# a101-fader.net
KiCad netlist of a schematic drawn in EAGLE
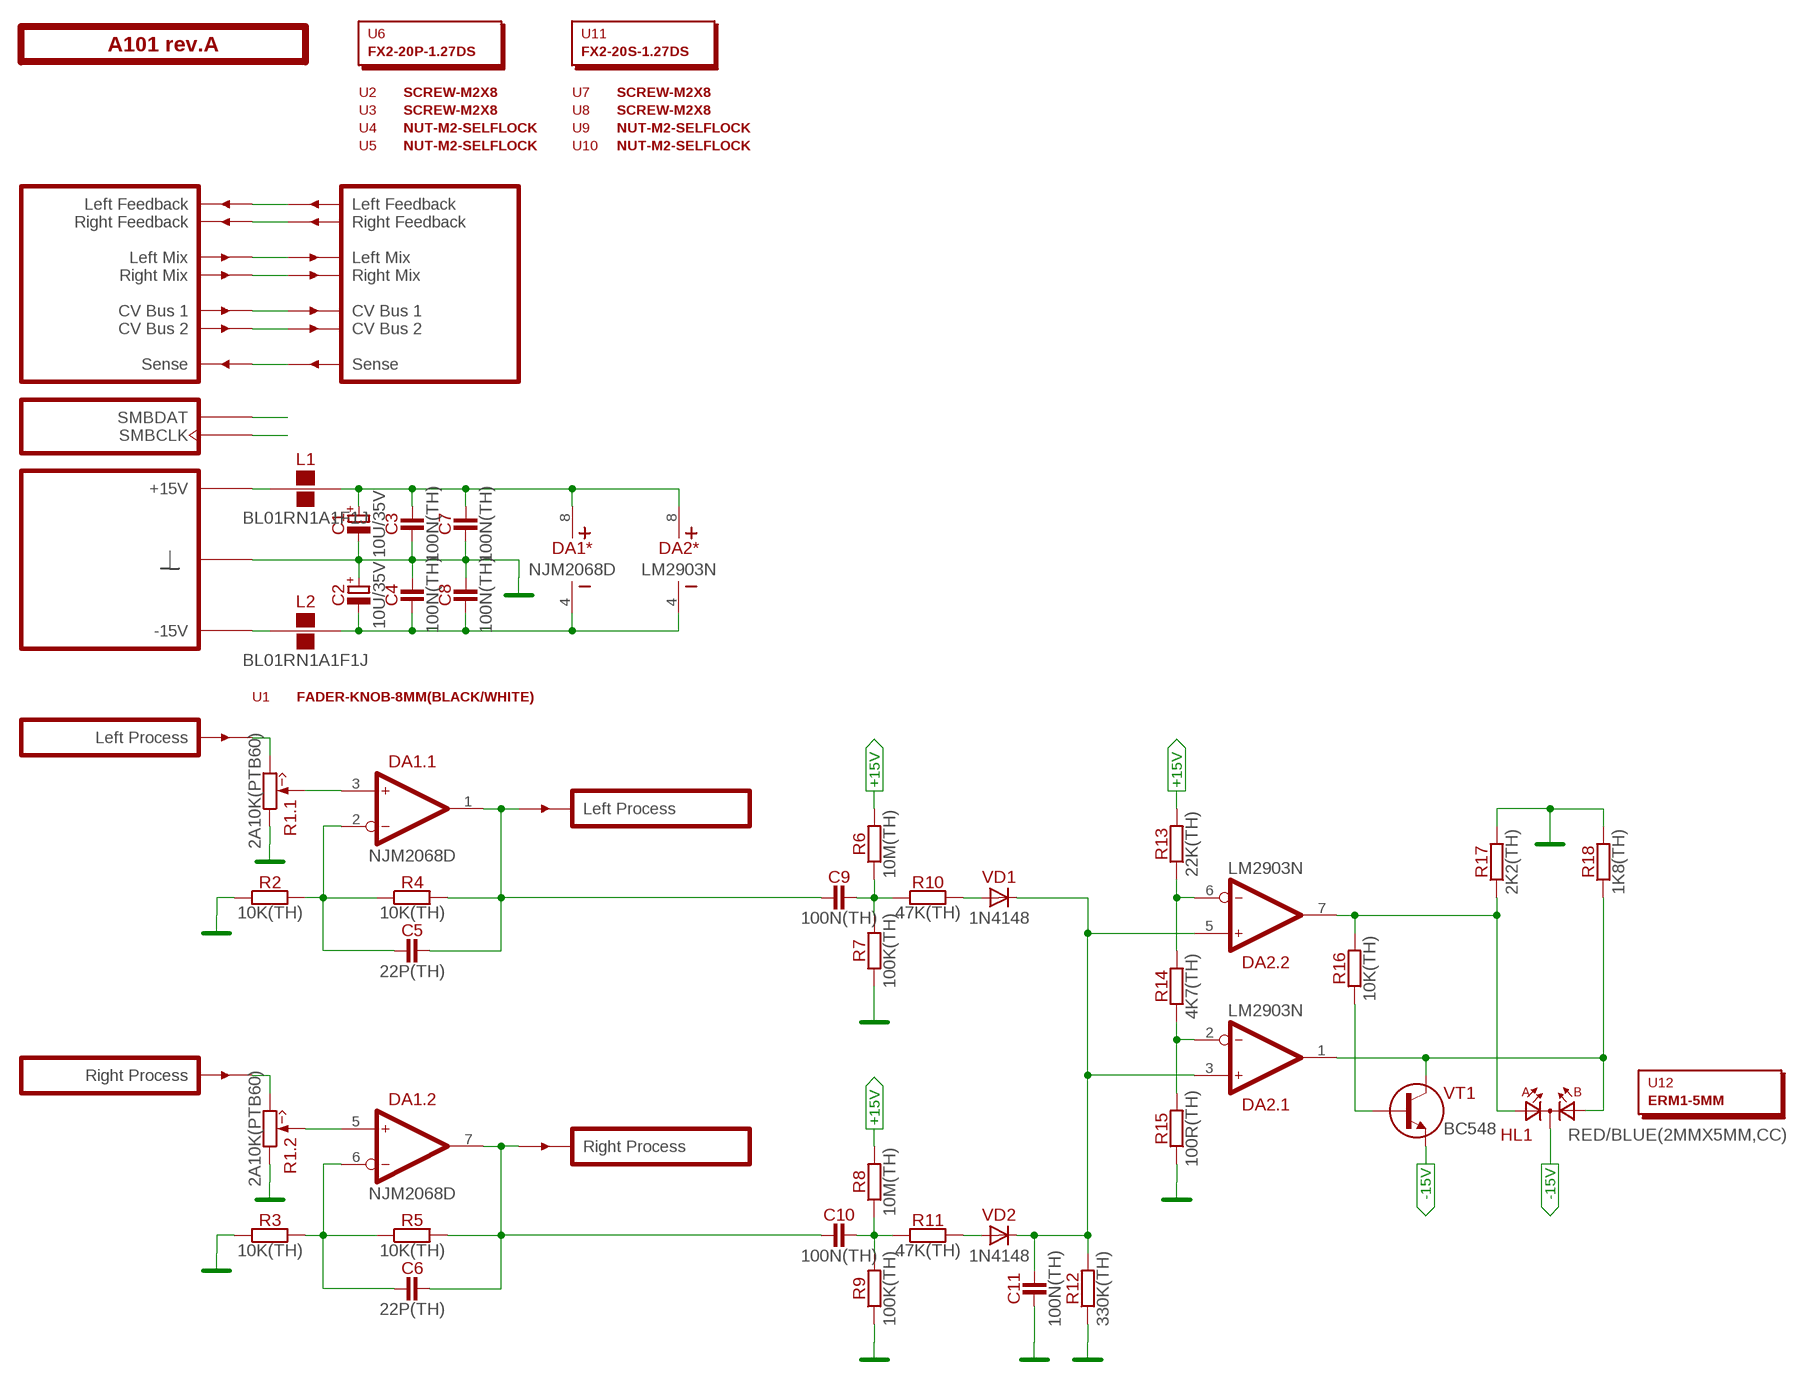
[diagram p0: schematic, sheet 1]

(export (version "E")
  (design (tool "Eeschema 10.0.6"))
  (components
    (comp (ref "C1")
      (value "10U/35V")
      (footprint "eagle-import:E2-5")
      (libsource (lib "eagle-import") (part "?10U/35V"))
    )
    (comp (ref "C2")
      (value "10U/35V")
      (footprint "eagle-import:E2-5")
      (libsource (lib "eagle-import") (part "?10U/35V"))
    )
    (comp (ref "C3")
      (value "100N(TH)")
      (footprint "eagle-import:C050-024X044")
      (libsource (lib "eagle-import") (part "?100N(TH)"))
    )
    (comp (ref "C4")
      (value "100N(TH)")
      (footprint "eagle-import:C050-024X044")
      (libsource (lib "eagle-import") (part "?100N(TH)"))
    )
    (comp (ref "C5")
      (value "22P(TH)")
      (footprint "eagle-import:C050-024X044")
      (libsource (lib "eagle-import") (part "?22P(TH)"))
    )
    (comp (ref "C6")
      (value "22P(TH)")
      (footprint "eagle-import:C050-024X044")
      (libsource (lib "eagle-import") (part "?22P(TH)"))
    )
    (comp (ref "C7")
      (value "100N(TH)")
      (footprint "eagle-import:C050-024X044")
      (libsource (lib "eagle-import") (part "?100N(TH)"))
    )
    (comp (ref "C8")
      (value "100N(TH)")
      (footprint "eagle-import:C050-024X044")
      (libsource (lib "eagle-import") (part "?100N(TH)"))
    )
    (comp (ref "C9")
      (value "100N(TH)")
      (footprint "eagle-import:C050-024X044")
      (libsource (lib "eagle-import") (part "?100N(TH)"))
    )
    (comp (ref "C10")
      (value "100N(TH)")
      (footprint "eagle-import:C050-024X044")
      (libsource (lib "eagle-import") (part "?100N(TH)"))
    )
    (comp (ref "C11")
      (value "100N(TH)")
      (footprint "eagle-import:C050-024X044")
      (libsource (lib "eagle-import") (part "?100N(TH)"))
    )
    (comp (ref "DA1")
      (value "NJM2068D")
      (footprint "eagle-import:DIP-8")
      (libsource (lib "eagle-import") (part "NJM2068D"))
    )
    (comp (ref "DA2")
      (value "LM2903N")
      (footprint "eagle-import:DIP-8")
      (libsource (lib "eagle-import") (part "LM2903N"))
    )
    (comp (ref "HL1")
      (value "RED/BLUE(2MMX5MM,CC)")
      (footprint "eagle-import:LED2X5-3PIN")
      (libsource (lib "eagle-import") (part "?(2MMX5MM,CC)RED/BLUE"))
    )
    (comp (ref "L1")
      (value "BL01RN1A1F1J")
      (footprint "eagle-import:BL01RN1A")
      (libsource (lib "eagle-import") (part "BL01RN1A?1F1J"))
    )
    (comp (ref "L2")
      (value "BL01RN1A1F1J")
      (footprint "eagle-import:BL01RN1A")
      (libsource (lib "eagle-import") (part "BL01RN1A?1F1J"))
    )
    (comp (ref "PCB1")
      (value "A101 rev.A")
      (footprint "eagle-import:ST2-BOARD-50")
      (libsource (lib "eagle-import") (part "ST2-BOARD-?50"))
    )
    (comp (ref "R1")
      (value "2A10K(PTB60)")
      (footprint "eagle-import:PTB6044")
      (libsource (lib "eagle-import") (part "2?(PTB60)A10K"))
    )
    (comp (ref "R2")
      (value "10K(TH)")
      (footprint "eagle-import:R-0207_10")
      (libsource (lib "eagle-import") (part "?10K(TH)"))
    )
    (comp (ref "R3")
      (value "10K(TH)")
      (footprint "eagle-import:R-0207_10")
      (libsource (lib "eagle-import") (part "?10K(TH)"))
    )
    (comp (ref "R4")
      (value "10K(TH)")
      (footprint "eagle-import:R-0207_10")
      (libsource (lib "eagle-import") (part "?10K(TH)"))
    )
    (comp (ref "R5")
      (value "10K(TH)")
      (footprint "eagle-import:R-0207_10")
      (libsource (lib "eagle-import") (part "?10K(TH)"))
    )
    (comp (ref "R6")
      (value "10M(TH)")
      (footprint "eagle-import:R-0207_10")
      (libsource (lib "eagle-import") (part "?10M(TH)"))
    )
    (comp (ref "R7")
      (value "100K(TH)")
      (footprint "eagle-import:R-0207_10")
      (libsource (lib "eagle-import") (part "?100K(TH)"))
    )
    (comp (ref "R8")
      (value "10M(TH)")
      (footprint "eagle-import:R-0207_10")
      (libsource (lib "eagle-import") (part "?10M(TH)"))
    )
    (comp (ref "R9")
      (value "100K(TH)")
      (footprint "eagle-import:R-0207_10")
      (libsource (lib "eagle-import") (part "?100K(TH)"))
    )
    (comp (ref "R10")
      (value "47K(TH)")
      (footprint "eagle-import:R-0207_10")
      (libsource (lib "eagle-import") (part "?47K(TH)"))
    )
    (comp (ref "R11")
      (value "47K(TH)")
      (footprint "eagle-import:R-0207_10")
      (libsource (lib "eagle-import") (part "?47K(TH)"))
    )
    (comp (ref "R12")
      (value "330K(TH)")
      (footprint "eagle-import:R-0207_10")
      (libsource (lib "eagle-import") (part "?330K(TH)"))
    )
    (comp (ref "R13")
      (value "22K(TH)")
      (footprint "eagle-import:R-0207_10")
      (libsource (lib "eagle-import") (part "?22K(TH)"))
    )
    (comp (ref "R14")
      (value "4K7(TH)")
      (footprint "eagle-import:R-0207_10")
      (libsource (lib "eagle-import") (part "?4K7(TH)"))
    )
    (comp (ref "R15")
      (value "100R(TH)")
      (footprint "eagle-import:R-0207_10")
      (libsource (lib "eagle-import") (part "?100R(TH)"))
    )
    (comp (ref "R16")
      (value "10K(TH)")
      (footprint "eagle-import:R-0207_10")
      (libsource (lib "eagle-import") (part "?10K(TH)"))
    )
    (comp (ref "R17")
      (value "2K2(TH)")
      (footprint "eagle-import:R-0207_10")
      (libsource (lib "eagle-import") (part "?2K2(TH)"))
    )
    (comp (ref "R18")
      (value "1K8(TH)")
      (footprint "eagle-import:R-0207_10")
      (libsource (lib "eagle-import") (part "?1K8(TH)"))
    )
    (comp (ref "U1")
      (value "FADER-KNOB-8MM(BLACK/WHITE)")
      (footprint "eagle-import:EMPTY")
      (libsource (lib "eagle-import") (part "?FADER-KNOB-8MM(BLACK/WHITE)"))
    )
    (comp (ref "U2")
      (value "SCREW-M2X8")
      (footprint "eagle-import:EMPTY")
      (libsource (lib "eagle-import") (part "?SCREW-M2X8"))
    )
    (comp (ref "U3")
      (value "SCREW-M2X8")
      (footprint "eagle-import:EMPTY")
      (libsource (lib "eagle-import") (part "?SCREW-M2X8"))
    )
    (comp (ref "U4")
      (value "NUT-M2-SELFLOCK")
      (footprint "eagle-import:EMPTY")
      (libsource (lib "eagle-import") (part "?NUT-M2-SELFLOCK"))
    )
    (comp (ref "U5")
      (value "NUT-M2-SELFLOCK")
      (footprint "eagle-import:EMPTY")
      (libsource (lib "eagle-import") (part "?NUT-M2-SELFLOCK"))
    )
    (comp (ref "U6")
      (value "FX2-20P-1.27DS")
      (footprint "eagle-import:EMPTY")
      (libsource (lib "eagle-import") (part "?FX2-20P-1.27DS"))
    )
    (comp (ref "U7")
      (value "SCREW-M2X8")
      (footprint "eagle-import:EMPTY")
      (libsource (lib "eagle-import") (part "?SCREW-M2X8"))
    )
    (comp (ref "U8")
      (value "SCREW-M2X8")
      (footprint "eagle-import:EMPTY")
      (libsource (lib "eagle-import") (part "?SCREW-M2X8"))
    )
    (comp (ref "U9")
      (value "NUT-M2-SELFLOCK")
      (footprint "eagle-import:EMPTY")
      (libsource (lib "eagle-import") (part "?NUT-M2-SELFLOCK"))
    )
    (comp (ref "U10")
      (value "NUT-M2-SELFLOCK")
      (footprint "eagle-import:EMPTY")
      (libsource (lib "eagle-import") (part "?NUT-M2-SELFLOCK"))
    )
    (comp (ref "U11")
      (value "FX2-20S-1.27DS")
      (footprint "eagle-import:EMPTY")
      (libsource (lib "eagle-import") (part "?FX2-20S-1.27DS"))
    )
    (comp (ref "U12")
      (value "ERM1-5MM")
      (footprint "eagle-import:EMPTY")
      (libsource (lib "eagle-import") (part "?ERM1-5MM"))
    )
    (comp (ref "VD1")
      (value "1N4148")
      (footprint "eagle-import:DO35-7")
      (libsource (lib "eagle-import") (part "?1N4148"))
    )
    (comp (ref "VD2")
      (value "1N4148")
      (footprint "eagle-import:DO35-7")
      (libsource (lib "eagle-import") (part "?1N4148"))
    )
    (comp (ref "VT1")
      (value "BC548")
      (footprint "eagle-import:TO92")
      (libsource (lib "eagle-import") (part "?BC548"))
    )
  )
  (nets
    (net (code "1") (name "+15V") (class "Default")
      (node (ref "R13") (pin "2") (pinfunction "2_2") (pintype "passive"))
      (node (ref "R6") (pin "2") (pinfunction "2_2") (pintype "passive"))
      (node (ref "R8") (pin "2") (pinfunction "2_2") (pintype "passive"))
    )
    (net (code "2") (name "-15V") (class "Default")
      (node (ref "HL1") (pin "K") (pinfunction "K_K") (pintype "passive"))
      (node (ref "VT1") (pin "3") (pinfunction "E_3") (pintype "passive"))
    )
    (net (code "3") (name "GND") (class "Default")
      (node (ref "C1") (pin "-") (pinfunction "-_-") (pintype "passive"))
      (node (ref "C11") (pin "1") (pinfunction "1_1") (pintype "passive"))
      (node (ref "C2") (pin "+") (pinfunction "+_+") (pintype "passive"))
      (node (ref "C3") (pin "1") (pinfunction "1_1") (pintype "passive"))
      (node (ref "C4") (pin "2") (pinfunction "2_2") (pintype "passive"))
      (node (ref "C7") (pin "1") (pinfunction "1_1") (pintype "passive"))
      (node (ref "C8") (pin "2") (pinfunction "2_2") (pintype "passive"))
      (node (ref "PCB1") (pin "B4") (pinfunction "GND_B4") (pintype "bidirectional"))
      (node (ref "PCB1") (pin "B4'") (pinfunction "GND_B4'") (pintype "bidirectional"))
      (node (ref "PCB1") (pin "B5") (pinfunction "GND_B5") (pintype "bidirectional"))
      (node (ref "PCB1") (pin "B5'") (pinfunction "GND_B5'") (pintype "bidirectional"))
      (node (ref "PCB1") (pin "B6") (pinfunction "GND_B6") (pintype "bidirectional"))
      (node (ref "PCB1") (pin "B6'") (pinfunction "GND_B6'") (pintype "bidirectional"))
      (node (ref "PCB1") (pin "B7") (pinfunction "GND_B7") (pintype "bidirectional"))
      (node (ref "PCB1") (pin "B7'") (pinfunction "GND_B7'") (pintype "bidirectional"))
      (node (ref "PCB1") (pin "B8") (pinfunction "GND_B8") (pintype "bidirectional"))
      (node (ref "PCB1") (pin "B8'") (pinfunction "GND_B8'") (pintype "bidirectional"))
      (node (ref "R1") (pin "A1") (pinfunction "CCW_A1") (pintype "passive"))
      (node (ref "R1") (pin "B1") (pinfunction "CCW_B1") (pintype "passive"))
      (node (ref "R12") (pin "1") (pinfunction "1_1") (pintype "passive"))
      (node (ref "R15") (pin "1") (pinfunction "1_1") (pintype "passive"))
      (node (ref "R17") (pin "2") (pinfunction "2_2") (pintype "passive"))
      (node (ref "R18") (pin "2") (pinfunction "2_2") (pintype "passive"))
      (node (ref "R2") (pin "1") (pinfunction "1_1") (pintype "passive"))
      (node (ref "R3") (pin "1") (pinfunction "1_1") (pintype "passive"))
      (node (ref "R7") (pin "1") (pinfunction "1_1") (pintype "passive"))
      (node (ref "R9") (pin "1") (pinfunction "1_1") (pintype "passive"))
    )
    (net (code "4") (name "Net-(C9-Pad2)") (class "Default")
      (node (ref "C9") (pin "2") (pinfunction "2_2") (pintype "passive"))
      (node (ref "R10") (pin "1") (pinfunction "1_1") (pintype "passive"))
      (node (ref "R6") (pin "1") (pinfunction "1_1") (pintype "passive"))
      (node (ref "R7") (pin "2") (pinfunction "2_2") (pintype "passive"))
    )
    (net (code "5") (name "Net-(C10-Pad2)") (class "Default")
      (node (ref "C10") (pin "2") (pinfunction "2_2") (pintype "passive"))
      (node (ref "R11") (pin "1") (pinfunction "1_1") (pintype "passive"))
      (node (ref "R8") (pin "1") (pinfunction "1_1") (pintype "passive"))
      (node (ref "R9") (pin "2") (pinfunction "2_2") (pintype "passive"))
    )
    (net (code "6") (name "Net-(DA1A-V+)") (class "Default")
      (node (ref "C1") (pin "+") (pinfunction "+_+") (pintype "passive"))
      (node (ref "C3") (pin "2") (pinfunction "2_2") (pintype "passive"))
      (node (ref "C7") (pin "2") (pinfunction "2_2") (pintype "passive"))
      (node (ref "DA1") (pin "8") (pinfunction "V+_8") (pintype "power_in"))
      (node (ref "DA2") (pin "8") (pinfunction "V+_8") (pintype "power_in"))
      (node (ref "L1") (pin "2") (pinfunction "2_2") (pintype "passive"))
    )
    (net (code "7") (name "Net-(DA1A-V-)") (class "Default")
      (node (ref "C2") (pin "-") (pinfunction "-_-") (pintype "passive"))
      (node (ref "C4") (pin "1") (pinfunction "1_1") (pintype "passive"))
      (node (ref "C8") (pin "1") (pinfunction "1_1") (pintype "passive"))
      (node (ref "DA1") (pin "4") (pinfunction "V-_4") (pintype "power_in"))
      (node (ref "DA2") (pin "4") (pinfunction "V-_4") (pintype "power_in"))
      (node (ref "L2") (pin "2") (pinfunction "2_2") (pintype "passive"))
    )
    (net (code "8") (name "Net-(DA1B-IN+)") (class "Default")
      (node (ref "DA1") (pin "3") (pinfunction "IN+_3") (pintype "input"))
      (node (ref "R1") (pin "A2") (pinfunction "W_A2") (pintype "passive"))
    )
    (net (code "9") (name "Net-(DA1B-IN-)") (class "Default")
      (node (ref "C5") (pin "1") (pinfunction "1_1") (pintype "passive"))
      (node (ref "DA1") (pin "2") (pinfunction "IN-_2") (pintype "input"))
      (node (ref "R2") (pin "2") (pinfunction "2_2") (pintype "passive"))
      (node (ref "R4") (pin "1") (pinfunction "1_1") (pintype "passive"))
    )
    (net (code "10") (name "Net-(DA1B-OUT)") (class "Default")
      (node (ref "C5") (pin "2") (pinfunction "2_2") (pintype "passive"))
      (node (ref "C9") (pin "1") (pinfunction "1_1") (pintype "passive"))
      (node (ref "DA1") (pin "1") (pinfunction "OUT_1") (pintype "output"))
      (node (ref "PCB1") (pin "BOUTL'") (pinfunction "OUTL_BOUTL'") (pintype "bidirectional"))
      (node (ref "R4") (pin "2") (pinfunction "2_2") (pintype "passive"))
    )
    (net (code "11") (name "Net-(DA1C-IN+)") (class "Default")
      (node (ref "DA1") (pin "5") (pinfunction "IN+_5") (pintype "input"))
      (node (ref "R1") (pin "B2") (pinfunction "W_B2") (pintype "passive"))
    )
    (net (code "12") (name "Net-(DA1C-IN-)") (class "Default")
      (node (ref "C6") (pin "1") (pinfunction "1_1") (pintype "passive"))
      (node (ref "DA1") (pin "6") (pinfunction "IN-_6") (pintype "input"))
      (node (ref "R3") (pin "2") (pinfunction "2_2") (pintype "passive"))
      (node (ref "R5") (pin "1") (pinfunction "1_1") (pintype "passive"))
    )
    (net (code "13") (name "Net-(DA1C-OUT)") (class "Default")
      (node (ref "C10") (pin "1") (pinfunction "1_1") (pintype "passive"))
      (node (ref "C6") (pin "2") (pinfunction "2_2") (pintype "passive"))
      (node (ref "DA1") (pin "7") (pinfunction "OUT_7") (pintype "output"))
      (node (ref "PCB1") (pin "BOUTR'") (pinfunction "OUTR_BOUTR'") (pintype "bidirectional"))
      (node (ref "R5") (pin "2") (pinfunction "2_2") (pintype "passive"))
    )
    (net (code "14") (name "Net-(DA2B-IN+)") (class "Default")
      (node (ref "C11") (pin "2") (pinfunction "2_2") (pintype "passive"))
      (node (ref "DA2") (pin "3") (pinfunction "IN+_3") (pintype "input"))
      (node (ref "DA2") (pin "5") (pinfunction "IN+_5") (pintype "input"))
      (node (ref "R12") (pin "2") (pinfunction "2_2") (pintype "passive"))
      (node (ref "VD1") (pin "C") (pinfunction "C_C") (pintype "passive"))
      (node (ref "VD2") (pin "C") (pinfunction "C_C") (pintype "passive"))
    )
    (net (code "15") (name "Net-(DA2B-IN-)") (class "Default")
      (node (ref "DA2") (pin "2") (pinfunction "IN-_2") (pintype "input"))
      (node (ref "R14") (pin "1") (pinfunction "1_1") (pintype "passive"))
      (node (ref "R15") (pin "2") (pinfunction "2_2") (pintype "passive"))
    )
    (net (code "16") (name "Net-(DA2B-OUT)") (class "Default")
      (node (ref "DA2") (pin "1") (pinfunction "OUT_1") (pintype "output"))
      (node (ref "HL1") (pin "A2") (pinfunction "A2_A2") (pintype "passive"))
      (node (ref "R18") (pin "1") (pinfunction "1_1") (pintype "passive"))
      (node (ref "VT1") (pin "1") (pinfunction "C_1") (pintype "passive"))
    )
    (net (code "17") (name "Net-(DA2C-IN-)") (class "Default")
      (node (ref "DA2") (pin "6") (pinfunction "IN-_6") (pintype "input"))
      (node (ref "R13") (pin "1") (pinfunction "1_1") (pintype "passive"))
      (node (ref "R14") (pin "2") (pinfunction "2_2") (pintype "passive"))
    )
    (net (code "18") (name "Net-(DA2C-OUT)") (class "Default")
      (node (ref "DA2") (pin "7") (pinfunction "OUT_7") (pintype "output"))
      (node (ref "HL1") (pin "A1") (pinfunction "A1_A1") (pintype "passive"))
      (node (ref "R16") (pin "2") (pinfunction "2_2") (pintype "passive"))
      (node (ref "R17") (pin "1") (pinfunction "1_1") (pintype "passive"))
    )
    (net (code "19") (name "Net-(L1-Pad1)") (class "Default")
      (node (ref "L1") (pin "1") (pinfunction "1_1") (pintype "passive"))
      (node (ref "PCB1") (pin "A+15") (pinfunction "P+15V_A+15") (pintype "bidirectional"))
      (node (ref "PCB1") (pin "A+15'") (pinfunction "P+15V_A+15'") (pintype "bidirectional"))
      (node (ref "PCB1") (pin "B+15") (pinfunction "P+15V_B+15") (pintype "bidirectional"))
      (node (ref "PCB1") (pin "B+15'") (pinfunction "P+15V_B+15'") (pintype "bidirectional"))
    )
    (net (code "20") (name "Net-(L2-Pad1)") (class "Default")
      (node (ref "L2") (pin "1") (pinfunction "1_1") (pintype "passive"))
      (node (ref "PCB1") (pin "A-15") (pinfunction "P-15V_A-15") (pintype "bidirectional"))
      (node (ref "PCB1") (pin "A-15'") (pinfunction "P-15V_A-15'") (pintype "bidirectional"))
      (node (ref "PCB1") (pin "B-15") (pinfunction "P-15V_B-15") (pintype "bidirectional"))
      (node (ref "PCB1") (pin "B-15'") (pinfunction "P-15V_B-15'") (pintype "bidirectional"))
    )
    (net (code "21") (name "Net-(PCB1B-INL)") (class "Default")
      (node (ref "PCB1") (pin "BINL") (pinfunction "INL_BINL") (pintype "bidirectional"))
      (node (ref "R1") (pin "A3") (pinfunction "CW_A3") (pintype "passive"))
    )
    (net (code "22") (name "Net-(PCB1C-INR)") (class "Default")
      (node (ref "PCB1") (pin "BINR") (pinfunction "INR_BINR") (pintype "bidirectional"))
      (node (ref "R1") (pin "B3") (pinfunction "CW_B3") (pintype "passive"))
    )
    (net (code "23") (name "Net-(PCB1F-CV1)") (class "Default")
      (node (ref "PCB1") (pin "ACV1") (pinfunction "CV1_ACV1") (pintype "bidirectional"))
      (node (ref "PCB1") (pin "ACV1'") (pinfunction "CV1'_ACV1'") (pintype "bidirectional"))
    )
    (net (code "24") (name "Net-(PCB1F-CV2)") (class "Default")
      (node (ref "PCB1") (pin "ACV2") (pinfunction "CV2_ACV2") (pintype "bidirectional"))
      (node (ref "PCB1") (pin "ACV2'") (pinfunction "CV2'_ACV2'") (pintype "bidirectional"))
    )
    (net (code "25") (name "Net-(PCB1F-LFBK)") (class "Default")
      (node (ref "PCB1") (pin "ALFBK") (pinfunction "LFBK_ALFBK") (pintype "bidirectional"))
      (node (ref "PCB1") (pin "ALFBK'") (pinfunction "LFBK'_ALFBK'") (pintype "bidirectional"))
    )
    (net (code "26") (name "Net-(PCB1F-LMIX)") (class "Default")
      (node (ref "PCB1") (pin "ALMIX") (pinfunction "LMIX_ALMIX") (pintype "bidirectional"))
      (node (ref "PCB1") (pin "ALMIX'") (pinfunction "LMIX'_ALMIX'") (pintype "bidirectional"))
    )
    (net (code "27") (name "Net-(PCB1F-RFBK)") (class "Default")
      (node (ref "PCB1") (pin "ARFBK") (pinfunction "RFBK_ARFBK") (pintype "bidirectional"))
      (node (ref "PCB1") (pin "ARFBK'") (pinfunction "RFBK'_ARFBK'") (pintype "bidirectional"))
    )
    (net (code "28") (name "Net-(PCB1F-RMIX)") (class "Default")
      (node (ref "PCB1") (pin "ARMIX") (pinfunction "RMIX_ARMIX") (pintype "bidirectional"))
      (node (ref "PCB1") (pin "ARMIX'") (pinfunction "RMIX'_ARMIX'") (pintype "bidirectional"))
    )
    (net (code "29") (name "Net-(PCB1F-SENSE)") (class "Default")
      (node (ref "PCB1") (pin "BSENSE") (pinfunction "SENSE_BSENSE") (pintype "bidirectional"))
      (node (ref "PCB1") (pin "BSENSE'") (pinfunction "SENSE'_BSENSE'") (pintype "bidirectional"))
    )
    (net (code "30") (name "Net-(PCB1H-SMBCLK-PadASMBCLK')") (class "Default")
      (node (ref "PCB1") (pin "ASMBCLK") (pinfunction "SMBCLK_ASMBCLK") (pintype "bidirectional"))
      (node (ref "PCB1") (pin "ASMBCLK'") (pinfunction "SMBCLK_ASMBCLK'") (pintype "bidirectional"))
    )
    (net (code "31") (name "Net-(PCB1H-SMBDAT-PadASMBDAT')") (class "Default")
      (node (ref "PCB1") (pin "ASMBDAT") (pinfunction "SMBDAT_ASMBDAT") (pintype "bidirectional"))
      (node (ref "PCB1") (pin "ASMBDAT'") (pinfunction "SMBDAT_ASMBDAT'") (pintype "bidirectional"))
    )
    (net (code "32") (name "Net-(R10-Pad2)") (class "Default")
      (node (ref "R10") (pin "2") (pinfunction "2_2") (pintype "passive"))
      (node (ref "VD1") (pin "A") (pinfunction "A_A") (pintype "passive"))
    )
    (net (code "33") (name "Net-(R11-Pad2)") (class "Default")
      (node (ref "R11") (pin "2") (pinfunction "2_2") (pintype "passive"))
      (node (ref "VD2") (pin "A") (pinfunction "A_A") (pintype "passive"))
    )
    (net (code "34") (name "Net-(VT1-B)") (class "Default")
      (node (ref "R16") (pin "1") (pinfunction "1_1") (pintype "passive"))
      (node (ref "VT1") (pin "2") (pinfunction "B_2") (pintype "passive"))
    )
  )
)
